# roco1044.net
KiCad netlist of a schematic drawn in EAGLE
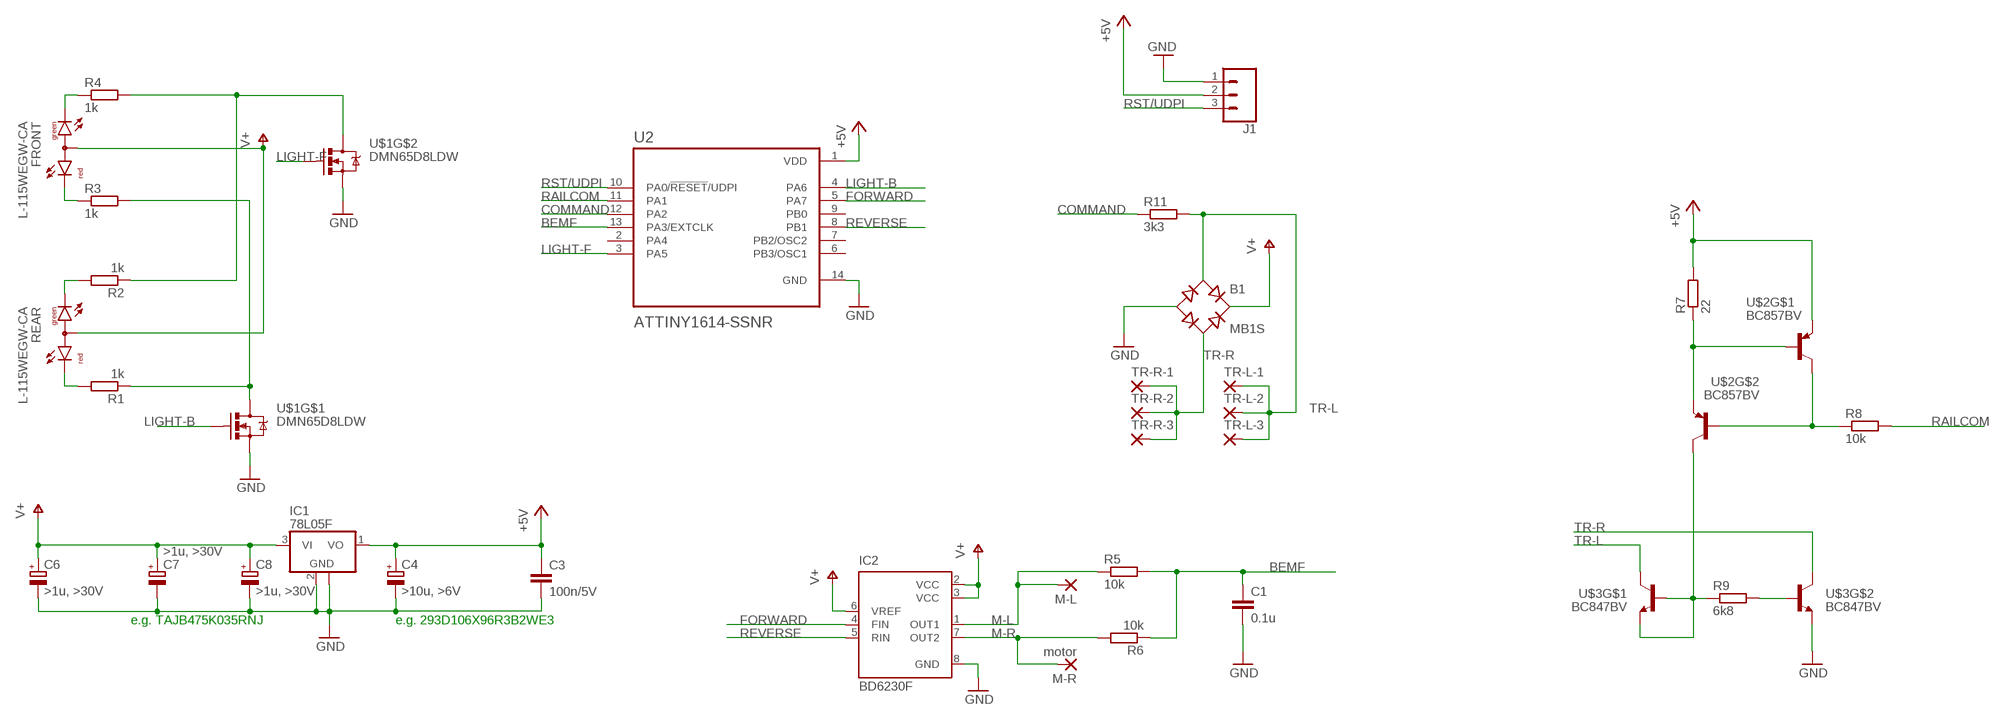
[diagram p0: schematic, sheet 1]

(export (version "E")
  (design (tool "Eeschema 10.0.6"))
  (components
    (comp (ref "B1")
      (value "MB1S")
      (footprint "eagle-import:SOIC-4")
      (libsource (lib "eagle-import") (part "MBS1"))
    )
    (comp (ref "C1")
      (value "0.1u")
      (footprint "eagle-import:C0805")
      (libsource (lib "eagle-import") (part "resistor_348_C-EUC0805"))
    )
    (comp (ref "C3")
      (value "100n/5V")
      (footprint "eagle-import:C0805")
      (libsource (lib "eagle-import") (part "C-EUC0805"))
    )
    (comp (ref "C4")
      (value ">10u, >6V")
      (footprint "eagle-import:CT3528")
      (libsource (lib "eagle-import") (part "CPOL-EUCT3528"))
    )
    (comp (ref "C6")
      (value ">1u, >30V")
      (footprint "eagle-import:CT3528")
      (libsource (lib "eagle-import") (part "CPOL-EUCT3528"))
    )
    (comp (ref "C7")
      (value ">1u, >30V")
      (footprint "eagle-import:CT3528")
      (libsource (lib "eagle-import") (part "CPOL-EUCT3528"))
    )
    (comp (ref "C8")
      (value ">1u, >30V")
      (footprint "eagle-import:CT3528")
      (libsource (lib "eagle-import") (part "CPOL-EUCT3528"))
    )
    (comp (ref "FRONT")
      (value "L-115WEGW-CA")
      (footprint "eagle-import:DUOLED-A-3MM")
      (libsource (lib "eagle-import") (part "L-115WEGW-CA"))
    )
    (comp (ref "IC1")
      (value "78L05F")
      (footprint "eagle-import:SOT89")
      (libsource (lib "eagle-import") (part "78LF05"))
    )
    (comp (ref "IC2")
      (value "BD6230F")
      (footprint "eagle-import:SOP8")
      (fields (field (name "MPN") "BD6230F-E2"))
      (libsource (lib "eagle-import") (part "BD623F0"))
    )
    (comp (ref "J1")
      (value "455-1750-1-ND")
      (footprint "eagle-import:1X03")
      (libsource (lib "eagle-import") (part "CONN_03"))
    )
    (comp (ref "M-L")
      (value "SMD5")
      (footprint "eagle-import:SMD2,54-5,08")
      (libsource (lib "eagle-import") (part "SMD5"))
    )
    (comp (ref "M-R")
      (value "motor")
      (footprint "eagle-import:SMD2,54-5,08")
      (libsource (lib "eagle-import") (part "SMD5"))
    )
    (comp (ref "R1")
      (value "1k")
      (footprint "eagle-import:R0805")
      (libsource (lib "eagle-import") (part "R-EU_R0805"))
    )
    (comp (ref "R2")
      (value "1k")
      (footprint "eagle-import:R0805")
      (libsource (lib "eagle-import") (part "R-EU_R0805"))
    )
    (comp (ref "R3")
      (value "1k")
      (footprint "eagle-import:R0805")
      (libsource (lib "eagle-import") (part "R-EU_R0805"))
    )
    (comp (ref "R4")
      (value "1k")
      (footprint "eagle-import:R0805")
      (libsource (lib "eagle-import") (part "R-EU_R0805"))
    )
    (comp (ref "R5")
      (value "10k")
      (footprint "eagle-import:R0805")
      (libsource (lib "eagle-import") (part "R-EU_R0805"))
    )
    (comp (ref "R6")
      (value "10k")
      (footprint "eagle-import:R0805")
      (libsource (lib "eagle-import") (part "R-EU_R0805"))
    )
    (comp (ref "R7")
      (value "22")
      (footprint "eagle-import:R0805")
      (libsource (lib "eagle-import") (part "R-EU_R0805"))
    )
    (comp (ref "R8")
      (value "10k")
      (footprint "eagle-import:R0805")
      (libsource (lib "eagle-import") (part "R-EU_R0805"))
    )
    (comp (ref "R9")
      (value "6k8")
      (footprint "eagle-import:R0805")
      (libsource (lib "eagle-import") (part "R-EU_R0805"))
    )
    (comp (ref "R11")
      (value "3k3")
      (footprint "eagle-import:R0805")
      (libsource (lib "eagle-import") (part "R-EU_R0805"))
    )
    (comp (ref "REAR")
      (value "L-115WEGW-CA")
      (footprint "eagle-import:DUOLED-A-3MM")
      (libsource (lib "eagle-import") (part "L-115WEGW-CA"))
    )
    (comp (ref "TR-L-1")
      (value "SMD5")
      (footprint "eagle-import:SMD2,54-5,08")
      (libsource (lib "eagle-import") (part "SMD5"))
    )
    (comp (ref "TR-L-2")
      (value "SMD5")
      (footprint "eagle-import:SMD2,54-5,08")
      (libsource (lib "eagle-import") (part "SMD5"))
    )
    (comp (ref "TR-L-3")
      (value "SMD5")
      (footprint "eagle-import:SMD2,54-5,08")
      (libsource (lib "eagle-import") (part "SMD5"))
    )
    (comp (ref "TR-R-1")
      (value "SMD5")
      (footprint "eagle-import:SMD2,54-5,08")
      (libsource (lib "eagle-import") (part "SMD5"))
    )
    (comp (ref "TR-R-2")
      (value "SMD5")
      (footprint "eagle-import:SMD2,54-5,08")
      (libsource (lib "eagle-import") (part "SMD5"))
    )
    (comp (ref "TR-R-3")
      (value "SMD5")
      (footprint "eagle-import:SMD2,54-5,08")
      (libsource (lib "eagle-import") (part "SMD5"))
    )
    (comp (ref "U$1")
      (value "DMN65D8LDW")
      (footprint "eagle-import:SOT363")
      (libsource (lib "eagle-import") (part "DMN65D8LDW"))
    )
    (comp (ref "U$2")
      (value "BC857BV")
      (footprint "eagle-import:SOT-666")
      (libsource (lib "eagle-import") (part "BC857BV"))
    )
    (comp (ref "U$3")
      (value "BC847BV")
      (footprint "eagle-import:SOT-666")
      (libsource (lib "eagle-import") (part "BC847BV"))
    )
    (comp (ref "U2")
      (value "ATTINY1614-SSNR")
      (footprint "eagle-import:SOIC127P600X175-14N")
      (fields (field (name "MF") "Microchip"))
      (libsource (lib "eagle-import") (part "ATTINY1614-SSNR"))
    )
  )
  (nets
    (net (code "1") (name "+5V") (class "Default")
      (node (ref "C3") (pin "1") (pinfunction "1_1") (pintype "passive"))
      (node (ref "C4") (pin "+") (pinfunction "+_+") (pintype "passive"))
      (node (ref "IC1") (pin "1") (pinfunction "VO_1") (pintype "passive"))
      (node (ref "J1") (pin "2") (pinfunction "2_2") (pintype "passive"))
      (node (ref "R7") (pin "2") (pinfunction "2_2") (pintype "passive"))
      (node (ref "U$2") (pin "P$1") (pinfunction "E_P$1") (pintype "passive"))
      (node (ref "U2") (pin "1") (pinfunction "VDD_1") (pintype "power_in"))
    )
    (net (code "2") (name "/BEMF") (class "Default")
      (node (ref "C1") (pin "1") (pinfunction "1_1") (pintype "passive"))
      (node (ref "R5") (pin "2") (pinfunction "2_2") (pintype "passive"))
      (node (ref "R6") (pin "1") (pinfunction "1_1") (pintype "passive"))
      (node (ref "U2") (pin "13") (pinfunction "PA3/EXTCLK_13") (pintype "bidirectional"))
    )
    (net (code "3") (name "/COMMAND") (class "Default")
      (node (ref "R11") (pin "1") (pinfunction "1_1") (pintype "passive"))
      (node (ref "U2") (pin "12") (pinfunction "PA2_12") (pintype "bidirectional"))
    )
    (net (code "4") (name "/FORWARD") (class "Default")
      (node (ref "IC2") (pin "4") (pinfunction "FIN_4") (pintype "input"))
      (node (ref "U2") (pin "5") (pinfunction "PA7_5") (pintype "bidirectional"))
    )
    (net (code "5") (name "/LIGHT-B") (class "Default")
      (node (ref "U$1") (pin "P$2") (pinfunction "G_P$2") (pintype "passive"))
      (node (ref "U2") (pin "4") (pinfunction "PA6_4") (pintype "bidirectional"))
    )
    (net (code "6") (name "/LIGHT-F") (class "Default")
      (node (ref "U$1") (pin "P$5") (pinfunction "G_P$5") (pintype "passive"))
      (node (ref "U2") (pin "3") (pinfunction "PA5_3") (pintype "bidirectional"))
    )
    (net (code "7") (name "/M-L") (class "Default")
      (node (ref "IC2") (pin "1") (pinfunction "OUT1_1") (pintype "output"))
      (node (ref "M-L") (pin "1") (pinfunction "P_1") (pintype "passive"))
      (node (ref "R5") (pin "1") (pinfunction "1_1") (pintype "passive"))
    )
    (net (code "8") (name "/M-R") (class "Default")
      (node (ref "IC2") (pin "7") (pinfunction "OUT2_7") (pintype "output"))
      (node (ref "M-R") (pin "1") (pinfunction "P_1") (pintype "passive"))
      (node (ref "R6") (pin "2") (pinfunction "2_2") (pintype "passive"))
    )
    (net (code "9") (name "/RAILCOM") (class "Default")
      (node (ref "R8") (pin "2") (pinfunction "2_2") (pintype "passive"))
      (node (ref "U2") (pin "11") (pinfunction "PA1_11") (pintype "bidirectional"))
    )
    (net (code "10") (name "/REVERSE") (class "Default")
      (node (ref "IC2") (pin "5") (pinfunction "RIN_5") (pintype "input"))
      (node (ref "U2") (pin "8") (pinfunction "PB1_8") (pintype "bidirectional"))
    )
    (net (code "11") (name "/RST{slash}UDPI") (class "Default")
      (node (ref "J1") (pin "3") (pinfunction "3_3") (pintype "passive"))
      (node (ref "U2") (pin "10") (pinfunction "PA0/~{RESET}/UDPI_10") (pintype "bidirectional"))
    )
    (net (code "12") (name "/TR-L") (class "Default")
      (node (ref "B1") (pin "~1") (pinfunction "AC1_~1") (pintype "passive"))
      (node (ref "R11") (pin "2") (pinfunction "2_2") (pintype "passive"))
      (node (ref "TR-L-1") (pin "1") (pinfunction "P_1") (pintype "passive"))
      (node (ref "TR-L-2") (pin "1") (pinfunction "P_1") (pintype "passive"))
      (node (ref "TR-L-3") (pin "1") (pinfunction "P_1") (pintype "passive"))
      (node (ref "U$3") (pin "P$6") (pinfunction "C_P$6") (pintype "passive"))
    )
    (net (code "13") (name "/TR-R") (class "Default")
      (node (ref "B1") (pin "~2") (pinfunction "AC2_~2") (pintype "passive"))
      (node (ref "TR-R-1") (pin "1") (pinfunction "P_1") (pintype "passive"))
      (node (ref "TR-R-2") (pin "1") (pinfunction "P_1") (pintype "passive"))
      (node (ref "TR-R-3") (pin "1") (pinfunction "P_1") (pintype "passive"))
      (node (ref "U$3") (pin "P$3") (pinfunction "C_P$3") (pintype "passive"))
    )
    (net (code "14") (name "GND") (class "Default")
      (node (ref "B1") (pin "-") (pinfunction "-_-") (pintype "passive"))
      (node (ref "C1") (pin "2") (pinfunction "2_2") (pintype "passive"))
      (node (ref "C3") (pin "2") (pinfunction "2_2") (pintype "passive"))
      (node (ref "C4") (pin "-") (pinfunction "-_-") (pintype "passive"))
      (node (ref "C6") (pin "-") (pinfunction "-_-") (pintype "passive"))
      (node (ref "C7") (pin "-") (pinfunction "-_-") (pintype "passive"))
      (node (ref "C8") (pin "-") (pinfunction "-_-") (pintype "passive"))
      (node (ref "IC1") (pin "2") (pinfunction "GND_2") (pintype "passive"))
      (node (ref "IC1") (pin "2@1") (pinfunction "GND_2@1") (pintype "passive"))
      (node (ref "IC2") (pin "8") (pinfunction "GND_8") (pintype "power_in"))
      (node (ref "J1") (pin "1") (pinfunction "1_1") (pintype "passive"))
      (node (ref "U$1") (pin "P$3") (pinfunction "S_P$3") (pintype "passive"))
      (node (ref "U$1") (pin "P$6") (pinfunction "S_P$6") (pintype "passive"))
      (node (ref "U$3") (pin "P$4") (pinfunction "E_P$4") (pintype "passive"))
      (node (ref "U2") (pin "14") (pinfunction "GND_14") (pintype "power_in"))
    )
    (net (code "15") (name "Net-(FRONT-CG)") (class "Default")
      (node (ref "FRONT") (pin "1") (pinfunction "CG_1") (pintype "passive"))
      (node (ref "R4") (pin "1") (pinfunction "1_1") (pintype "passive"))
    )
    (net (code "16") (name "Net-(FRONT-CR)") (class "Default")
      (node (ref "FRONT") (pin "3") (pinfunction "CR_3") (pintype "passive"))
      (node (ref "R3") (pin "1") (pinfunction "1_1") (pintype "passive"))
    )
    (net (code "17") (name "Net-(REAR-CG)") (class "Default")
      (node (ref "R2") (pin "2") (pinfunction "2_2") (pintype "passive"))
      (node (ref "REAR") (pin "1") (pinfunction "CG_1") (pintype "passive"))
    )
    (net (code "18") (name "Net-(REAR-CR)") (class "Default")
      (node (ref "R1") (pin "2") (pinfunction "2_2") (pintype "passive"))
      (node (ref "REAR") (pin "3") (pinfunction "CR_3") (pintype "passive"))
    )
    (net (code "19") (name "Net-(U$1A-D)") (class "Default")
      (node (ref "R1") (pin "1") (pinfunction "1_1") (pintype "passive"))
      (node (ref "R3") (pin "2") (pinfunction "2_2") (pintype "passive"))
      (node (ref "U$1") (pin "P$4") (pinfunction "D_P$4") (pintype "passive"))
    )
    (net (code "20") (name "Net-(U$1B-D)") (class "Default")
      (node (ref "R2") (pin "1") (pinfunction "1_1") (pintype "passive"))
      (node (ref "R4") (pin "2") (pinfunction "2_2") (pintype "passive"))
      (node (ref "U$1") (pin "P$1") (pinfunction "D_P$1") (pintype "passive"))
    )
    (net (code "21") (name "Net-(U$2A-B)") (class "Default")
      (node (ref "R7") (pin "1") (pinfunction "1_1") (pintype "passive"))
      (node (ref "U$2") (pin "P$2") (pinfunction "B_P$2") (pintype "passive"))
      (node (ref "U$2") (pin "P$4") (pinfunction "E_P$4") (pintype "passive"))
    )
    (net (code "22") (name "Net-(U$2A-C)") (class "Default")
      (node (ref "R8") (pin "1") (pinfunction "1_1") (pintype "passive"))
      (node (ref "U$2") (pin "P$5") (pinfunction "B_P$5") (pintype "passive"))
      (node (ref "U$2") (pin "P$6") (pinfunction "C_P$6") (pintype "passive"))
    )
    (net (code "23") (name "Net-(U$2B-C)") (class "Default")
      (node (ref "R9") (pin "1") (pinfunction "1_1") (pintype "passive"))
      (node (ref "U$2") (pin "P$3") (pinfunction "C_P$3") (pintype "passive"))
      (node (ref "U$3") (pin "P$1") (pinfunction "E_P$1") (pintype "passive"))
      (node (ref "U$3") (pin "P$2") (pinfunction "B_P$2") (pintype "passive"))
    )
    (net (code "24") (name "Net-(U$3B-B)") (class "Default")
      (node (ref "R9") (pin "2") (pinfunction "2_2") (pintype "passive"))
      (node (ref "U$3") (pin "P$5") (pinfunction "B_P$5") (pintype "passive"))
    )
    (net (code "25") (name "V+") (class "Default")
      (node (ref "B1") (pin "+") (pinfunction "+_+") (pintype "passive"))
      (node (ref "C6") (pin "+") (pinfunction "+_+") (pintype "passive"))
      (node (ref "C7") (pin "+") (pinfunction "+_+") (pintype "passive"))
      (node (ref "C8") (pin "+") (pinfunction "+_+") (pintype "passive"))
      (node (ref "FRONT") (pin "2") (pinfunction "A_2") (pintype "passive"))
      (node (ref "IC1") (pin "3") (pinfunction "VI_3") (pintype "input"))
      (node (ref "IC2") (pin "2") (pinfunction "VCC_2") (pintype "power_in"))
      (node (ref "IC2") (pin "3") (pinfunction "VCC_3") (pintype "power_in"))
      (node (ref "IC2") (pin "6") (pinfunction "VREF_6") (pintype "passive"))
      (node (ref "REAR") (pin "2") (pinfunction "A_2") (pintype "passive"))
    )
    (net (code "26") (name "unconnected-(U2-PA4-Pad2)") (class "Default")
      (node (ref "U2") (pin "2") (pinfunction "PA4_2") (pintype "bidirectional"))
    )
    (net (code "27") (name "unconnected-(U2-PB0-Pad9)") (class "Default")
      (node (ref "U2") (pin "9") (pinfunction "PB0_9") (pintype "bidirectional"))
    )
    (net (code "28") (name "unconnected-(U2-PB2{slash}OSC2-Pad7)") (class "Default")
      (node (ref "U2") (pin "7") (pinfunction "PB2/OSC2_7") (pintype "bidirectional"))
    )
    (net (code "29") (name "unconnected-(U2-PB3{slash}OSC1-Pad6)") (class "Default")
      (node (ref "U2") (pin "6") (pinfunction "PB3/OSC1_6") (pintype "bidirectional"))
    )
  )
)
